# Sheet1.net
KiCad netlist of a schematic drawn in Altium Designer
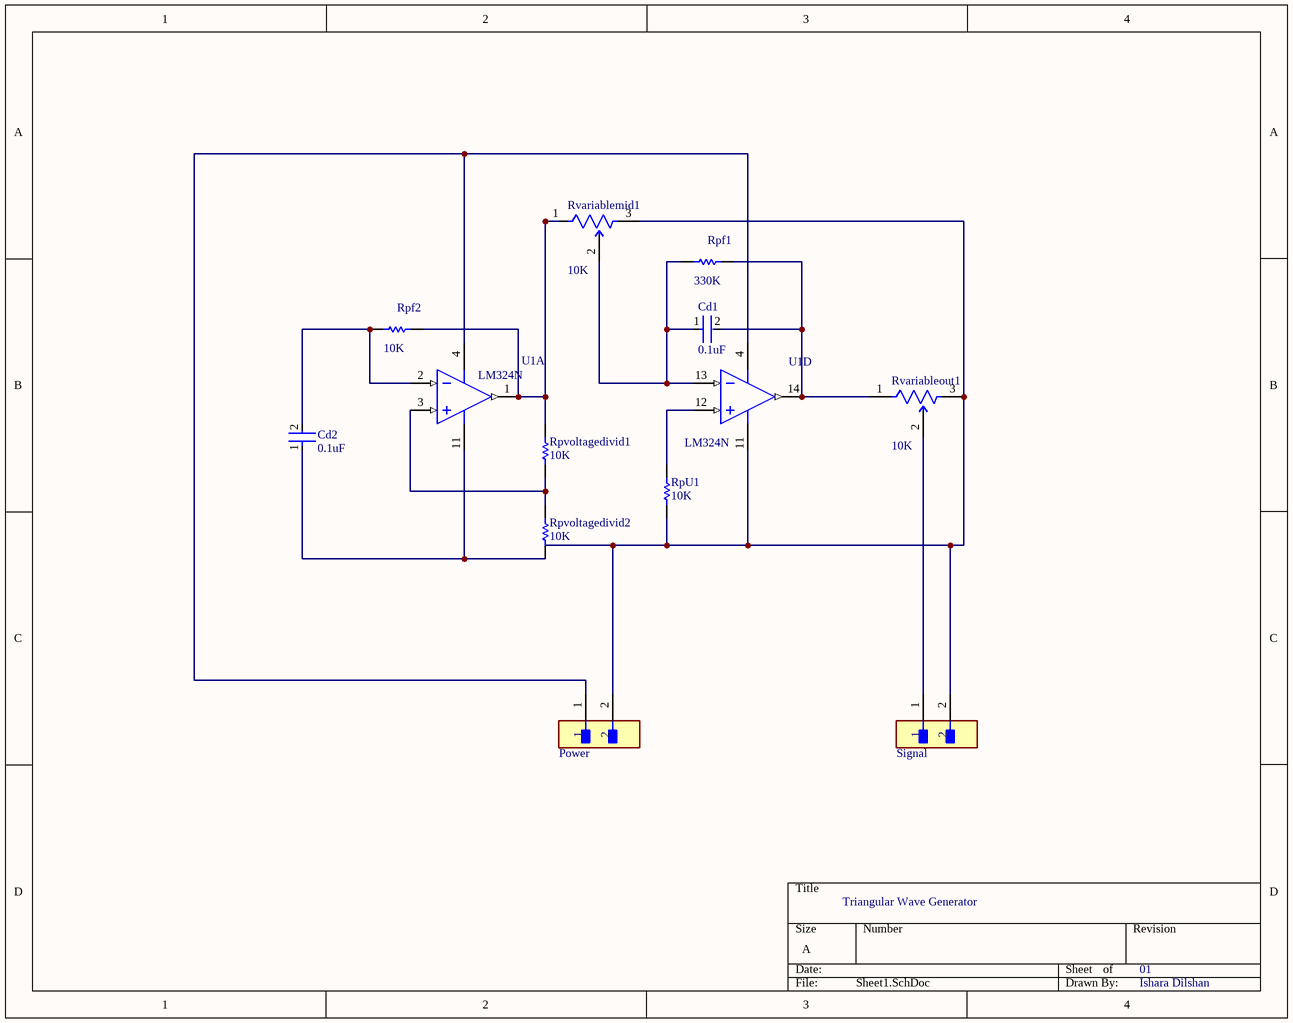
[diagram p0: Sheet1.SchDoc]

(export (version "E")
  (design (tool "Eeschema 10.0.6"))
  (components
    (comp (ref "Cd1")
      (value "0.1uF")
      (footprint "FP-RCE0K1-MFG")
      (description "Cap Ceramic 27pF 50V C0G ±5% Radial 5mm +125°C Automotive Bulk")
      (fields (field (name "TOLERANCE") "5%"))
      (libsource (lib "Altium Content Vault") (part "b4654b650e69147ec39a6b967a45e02"))
    )
    (comp (ref "Cd2")
      (value "0.1uF")
      (footprint "FP-RCE0K1-MFG")
      (description "Cap Ceramic 27pF 50V C0G ±5% Radial 5mm +125°C Automotive Bulk")
      (fields (field (name "TOLERANCE") "5%"))
      (libsource (lib "Altium Content Vault") (part "b4654b650e69147ec39a6b967a45e02"))
    )
    (comp (ref "Power")
      (value "~")
      (footprint "FP-B2B-XH-A_LF_SN-MFG")
      (description "CONN HEADER VERT 2POS 2.5MM")
      (libsource (lib "Altium Content Vault") (part "3bc925449376181038e59eaffc5286c"))
    )
    (comp (ref "Rpf1")
      (value "330K")
      (footprint "OMTE-RES7X2.5-2")
      (fields
        (field (name "TOLERANCE") "±5%")
        (field (name "PARTNUMBER") "OD103JE")
        (field (name "MANUFACTURER") "Ohmite")
      )
      (libsource (lib "Altium Content Vault") (part "RES-2"))
    )
    (comp (ref "Rpf2")
      (value "10K")
      (footprint "OMTE-RES7X2.5-2")
      (fields
        (field (name "TOLERANCE") "±5%")
        (field (name "PARTNUMBER") "OD103JE")
        (field (name "MANUFACTURER") "Ohmite")
      )
      (libsource (lib "Altium Content Vault") (part "RES-2"))
    )
    (comp (ref "RpU1")
      (value "10K")
      (footprint "OMTE-RES7X2.5-2")
      (fields
        (field (name "TOLERANCE") "±5%")
        (field (name "PARTNUMBER") "OD103JE")
        (field (name "MANUFACTURER") "Ohmite")
      )
      (libsource (lib "Altium Content Vault") (part "RES-2"))
    )
    (comp (ref "Rpvoltagedivid1")
      (value "10K")
      (footprint "OMTE-RES7X2.5-2")
      (fields
        (field (name "TOLERANCE") "±5%")
        (field (name "PARTNUMBER") "OD103JE")
        (field (name "MANUFACTURER") "Ohmite")
      )
      (libsource (lib "Altium Content Vault") (part "RES-2"))
    )
    (comp (ref "Rpvoltagedivid2")
      (value "10K")
      (footprint "OMTE-RES7X2.5-2")
      (fields
        (field (name "TOLERANCE") "±5%")
        (field (name "PARTNUMBER") "OD103JE")
        (field (name "MANUFACTURER") "Ohmite")
      )
      (libsource (lib "Altium Content Vault") (part "RES-2"))
    )
    (comp (ref "Rvariablemid1")
      (value "10K")
      (footprint "FP-3296W-MFG")
      (description "TRIMMER 50K OHM 0.5W PC PIN TOP")
      (fields (field (name "TOLERANCE") "10%"))
      (libsource (lib "Altium Content Vault") (part "2dcfd2547301a7d3209a5e99acfd772"))
    )
    (comp (ref "Rvariableout1")
      (value "10K")
      (footprint "FP-3296W-MFG")
      (description "TRIMMER 50K OHM 0.5W PC PIN TOP")
      (fields (field (name "TOLERANCE") "10%"))
      (libsource (lib "Altium Content Vault") (part "2dcfd2547301a7d3209a5e99acfd772"))
    )
    (comp (ref "Signal")
      (value "~")
      (footprint "FP-B2B-XH-A_LF_SN-MFG")
      (description "CONN HEADER VERT 2POS 2.5MM")
      (libsource (lib "Altium Content Vault") (part "3bc925449376181038e59eaffc5286c"))
    )
    (comp (ref "U1")
      (value "LM324N")
      (footprint "N0014A")
      (description "Low Power Quad Operational Amplifier, 14-pin MDIP")
      (fields (field (name "MANUFACTURER") "Texas Instruments"))
      (libsource (lib "Altium Content Vault") (part "AMP-OPA-LM124-14"))
    )
  )
  (nets
    (net (code "1") (name "Net-(Rvariablemid1-CCW)") (class "Default")
      (node (ref "Rpf2") (pin "2") (pinfunction "2_2") (pintype "passive"))
      (node (ref "Rpvoltagedivid1") (pin "2") (pinfunction "2_2") (pintype "passive"))
      (node (ref "Rvariablemid1") (pin "1") (pinfunction "CCW_1") (pintype "passive"))
      (node (ref "U1") (pin "1") (pinfunction "OUT1_1") (pintype "output"))
    )
    (net (code "2") (name "Net-(Rvariablemid1-CW)") (class "Default")
      (node (ref "Power") (pin "2") (pinfunction "2_2") (pintype "passive"))
      (node (ref "RpU1") (pin "1") (pinfunction "1_1") (pintype "passive"))
      (node (ref "Rvariablemid1") (pin "3") (pinfunction "CW_3") (pintype "passive"))
      (node (ref "Rvariableout1") (pin "3") (pinfunction "CW_3") (pintype "passive"))
      (node (ref "Signal") (pin "2") (pinfunction "2_2") (pintype "passive"))
      (node (ref "U1") (pin "11") (pinfunction "GND_11") (pintype "power_in"))
    )
    (net (code "3") (name "Net-(Rvariablemid1-WIPER)") (class "Default")
      (node (ref "Cd1") (pin "1") (pinfunction "1_1") (pintype "passive"))
      (node (ref "Rpf1") (pin "1") (pinfunction "1_1") (pintype "passive"))
      (node (ref "Rvariablemid1") (pin "2") (pinfunction "WIPER_2") (pintype "passive"))
      (node (ref "U1") (pin "13") (pinfunction "IN4-_13") (pintype "input"))
    )
    (net (code "4") (name "Net-(Rvariableout1-CCW)") (class "Default")
      (node (ref "Cd1") (pin "2") (pinfunction "2_2") (pintype "passive"))
      (node (ref "Rpf1") (pin "2") (pinfunction "2_2") (pintype "passive"))
      (node (ref "Rvariableout1") (pin "1") (pinfunction "CCW_1") (pintype "passive"))
      (node (ref "U1") (pin "14") (pinfunction "OUT4_14") (pintype "output"))
    )
    (net (code "5") (name "Net-(Rvariableout1-WIPER)") (class "Default")
      (node (ref "Rvariableout1") (pin "2") (pinfunction "WIPER_2") (pintype "passive"))
      (node (ref "Signal") (pin "1") (pinfunction "1_1") (pintype "passive"))
    )
    (net (code "6") (name "Net-(U1A-GND)") (class "Default")
      (node (ref "Cd2") (pin "1") (pinfunction "1_1") (pintype "passive"))
      (node (ref "Rpvoltagedivid2") (pin "1") (pinfunction "1_1") (pintype "passive"))
      (node (ref "U1") (pin "11") (pinfunction "GND_11") (pintype "power_in"))
    )
    (net (code "7") (name "Net-(U1A-IN1+)") (class "Default")
      (node (ref "Rpvoltagedivid1") (pin "1") (pinfunction "1_1") (pintype "passive"))
      (node (ref "Rpvoltagedivid2") (pin "2") (pinfunction "2_2") (pintype "passive"))
      (node (ref "U1") (pin "3") (pinfunction "IN1+_3") (pintype "input"))
    )
    (net (code "8") (name "Net-(U1A-IN1-)") (class "Default")
      (node (ref "Cd2") (pin "2") (pinfunction "2_2") (pintype "passive"))
      (node (ref "Rpf2") (pin "1") (pinfunction "1_1") (pintype "passive"))
      (node (ref "U1") (pin "2") (pinfunction "IN1-_2") (pintype "input"))
    )
    (net (code "9") (name "Net-(U1A-V+)") (class "Default")
      (node (ref "Power") (pin "1") (pinfunction "1_1") (pintype "passive"))
      (node (ref "U1") (pin "4") (pinfunction "V+_4") (pintype "power_in"))
    )
    (net (code "10") (name "Net-(U1D-IN4+)") (class "Default")
      (node (ref "RpU1") (pin "2") (pinfunction "2_2") (pintype "passive"))
      (node (ref "U1") (pin "12") (pinfunction "IN4+_12") (pintype "input"))
    )
  )
)
